# MP-Ethernet.net
KiCad netlist of a schematic drawn in Altium Designer
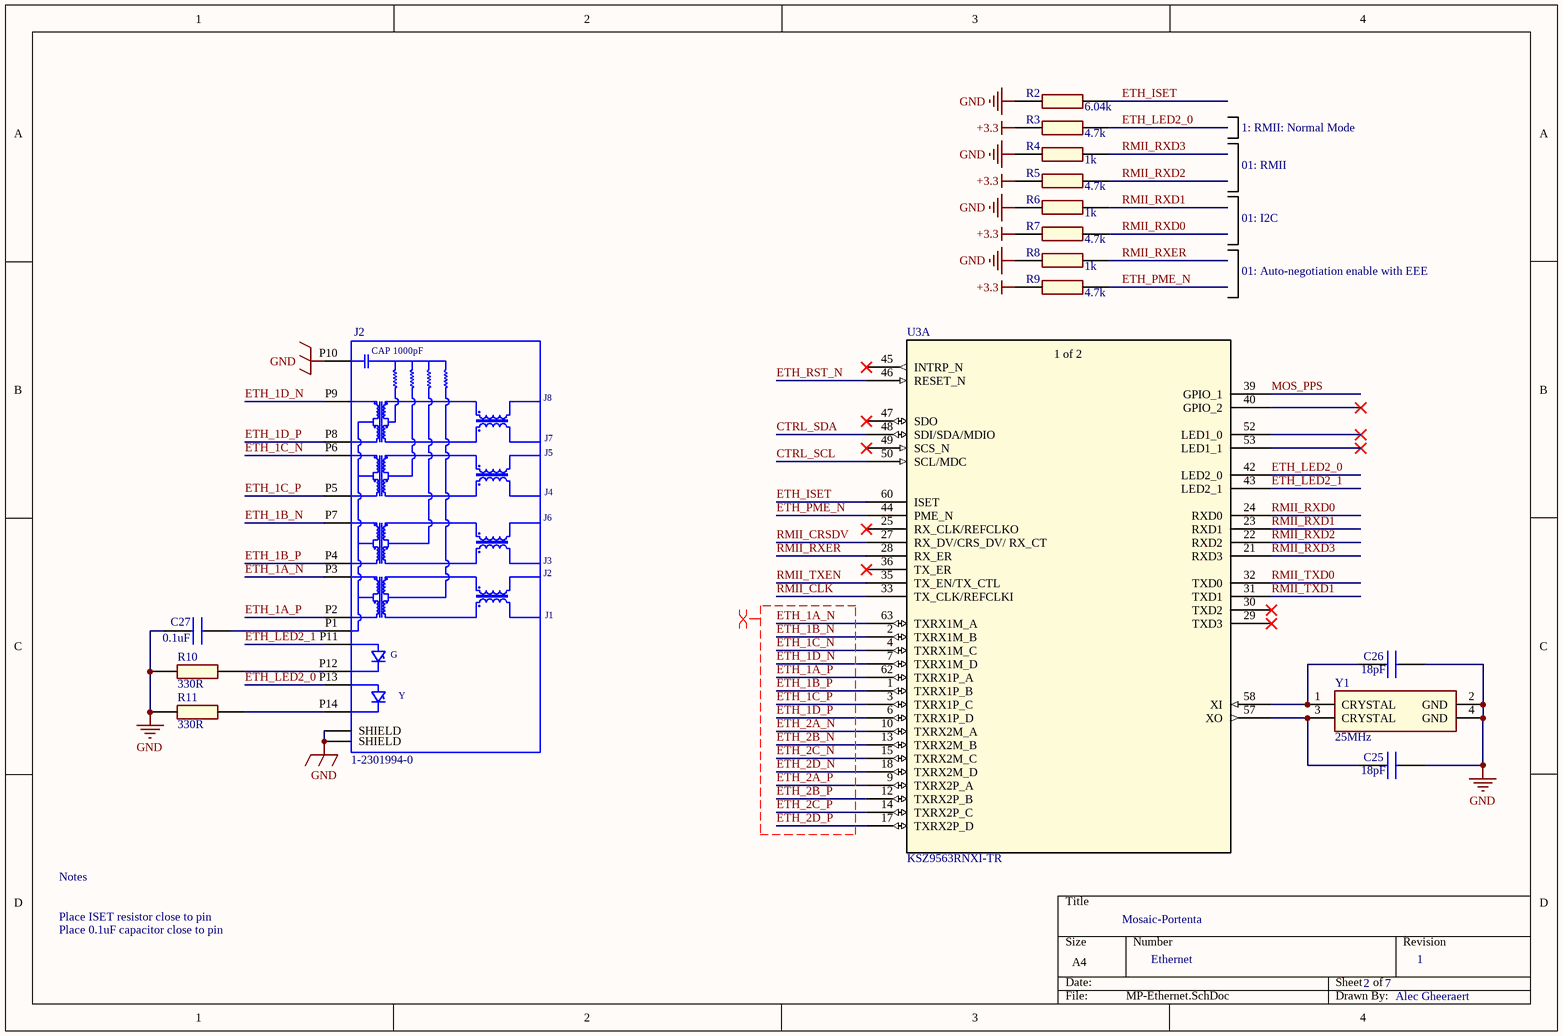
[diagram p0: MP-Ethernet.SchDoc]

(export (version "E")
  (design (tool "Eeschema 10.0.6"))
  (components
    (comp (ref "C25")
      (value "18pF")
      (footprint "CAPC1608X87N")
      (description "0603 18pF")
      (fields (field (name "TOLERANCE") "5%") (field (name "MANUFACTURER") "Walsin"))
      (libsource (lib "Ghrt") (part "0603N180J160CT"))
    )
    (comp (ref "C26")
      (value "18pF")
      (footprint "CAPC1608X87N")
      (description "0603 18pF")
      (fields (field (name "TOLERANCE") "5%") (field (name "MANUFACTURER") "Walsin"))
      (libsource (lib "Ghrt") (part "0603N180J160CT"))
    )
    (comp (ref "C27")
      (value "0.1uF")
      (footprint "CAPC2012X145N")
      (description "0805I 0.1µF")
      (fields (field (name "MANUFACTURER") "Walsin") (field (name "TOLERANCE") "10%"))
      (libsource (lib "Ghrt") (part "MG21B104K101CT"))
    )
    (comp (ref "J2")
      (value "1-2301994-0")
      (footprint "1-2301994-0")
      (description "RJ45 1Gbit MJ")
      (fields (field (name "MANUFACTURER") "TE Connectivity"))
      (libsource (lib "Ghrt") (part "1-2301994-0"))
    )
    (comp (ref "R2")
      (value "6.04k")
      (footprint "RESC1005X40N")
      (description "0402I 6.04k")
      (fields (field (name "MANUFACTURER") "Walsin") (field (name "TOLERANCE") "1%"))
      (libsource (lib "Ghrt") (part "WR04X6041FTL"))
    )
    (comp (ref "R3")
      (value "4.7k")
      (footprint "RESC1005X40N")
      (description "0402I 4.7k")
      (fields (field (name "MANUFACTURER") "Walsin") (field (name "TOLERANCE") "1%"))
      (libsource (lib "Ghrt") (part "WR04X4701FTL"))
    )
    (comp (ref "R4")
      (value "1k")
      (footprint "RESC1005X40N")
      (description "0402I 1k")
      (fields (field (name "MANUFACTURER") "Walsin") (field (name "TOLERANCE") "1%"))
      (libsource (lib "Ghrt") (part "WR04X1001FTL"))
    )
    (comp (ref "R5")
      (value "4.7k")
      (footprint "RESC1005X40N")
      (description "0402I 4.7k")
      (fields (field (name "MANUFACTURER") "Walsin") (field (name "TOLERANCE") "1%"))
      (libsource (lib "Ghrt") (part "WR04X4701FTL"))
    )
    (comp (ref "R6")
      (value "1k")
      (footprint "RESC1005X40N")
      (description "0402I 1k")
      (fields (field (name "MANUFACTURER") "Walsin") (field (name "TOLERANCE") "1%"))
      (libsource (lib "Ghrt") (part "WR04X1001FTL"))
    )
    (comp (ref "R7")
      (value "4.7k")
      (footprint "RESC1005X40N")
      (description "0402I 4.7k")
      (fields (field (name "MANUFACTURER") "Walsin") (field (name "TOLERANCE") "1%"))
      (libsource (lib "Ghrt") (part "WR04X4701FTL"))
    )
    (comp (ref "R8")
      (value "1k")
      (footprint "RESC1005X40N")
      (description "0402I 1k")
      (fields (field (name "MANUFACTURER") "Walsin") (field (name "TOLERANCE") "1%"))
      (libsource (lib "Ghrt") (part "WR04X1001FTL"))
    )
    (comp (ref "R9")
      (value "4.7k")
      (footprint "RESC1005X40N")
      (description "0402I 4.7k")
      (fields (field (name "MANUFACTURER") "Walsin") (field (name "TOLERANCE") "1%"))
      (libsource (lib "Ghrt") (part "WR04X4701FTL"))
    )
    (comp (ref "R10")
      (value "330R")
      (footprint "RESC1005X40N")
      (description "0402I 330")
      (fields (field (name "TOLERANCE") "1%") (field (name "MANUFACTURER") "Walsin"))
      (libsource (lib "Ghrt") (part "WR04X3300FTL"))
    )
    (comp (ref "R11")
      (value "330R")
      (footprint "RESC1005X40N")
      (description "0402I 330")
      (fields (field (name "TOLERANCE") "1%") (field (name "MANUFACTURER") "Walsin"))
      (libsource (lib "Ghrt") (part "WR04X3300FTL"))
    )
    (comp (ref "U3")
      (value "KSZ9563RNXI-TR")
      (footprint "VQFN64_NX_MCH")
      (description "3-Port Gigabit Ethernet Switch")
      (fields (field (name "MANUFACTURER") "Texas Instruments"))
      (libsource (lib "Ghrt") (part "KSZ9563RNXI-TR"))
    )
    (comp (ref "Y1")
      (value "25MHz")
      (footprint "LFXTAL055474REEL")
      (description "25MHz +/-50ppm Crystal")
      (fields (field (name "MANUFACTURER") "IQD") (field (name "TOLERANCE") "50PPM"))
      (libsource (lib "Ghrt") (part "LFXTAL055474REEL"))
    )
  )
  (nets
    (net (code "1") (name "+3.3") (class "Default")
      (node (ref "R3") (pin "1") (pinfunction "1_1") (pintype "passive"))
      (node (ref "R5") (pin "1") (pinfunction "1_1") (pintype "passive"))
      (node (ref "R7") (pin "1") (pinfunction "1_1") (pintype "passive"))
      (node (ref "R9") (pin "1") (pinfunction "1_1") (pintype "passive"))
    )
    (net (code "2") (name "/CTRL_SCL") (class "Default")
      (node (ref "U3") (pin "50") (pinfunction "SCL/MDC_50") (pintype "input"))
    )
    (net (code "3") (name "/CTRL_SDA") (class "Default")
      (node (ref "U3") (pin "48") (pinfunction "SDI/SDA/MDIO_48") (pintype "bidirectional"))
    )
    (net (code "4") (name "/ETH_1A_N") (class "Default")
      (node (ref "J2") (pin "P3") (pinfunction "P3_P3") (pintype "passive"))
      (node (ref "U3") (pin "63") (pinfunction "TXRX1M_A_63") (pintype "bidirectional"))
    )
    (net (code "5") (name "/ETH_1A_P") (class "Default")
      (node (ref "J2") (pin "P2") (pinfunction "P2_P2") (pintype "passive"))
      (node (ref "U3") (pin "62") (pinfunction "TXRX1P_A_62") (pintype "bidirectional"))
    )
    (net (code "6") (name "/ETH_1B_N") (class "Default")
      (node (ref "J2") (pin "P7") (pinfunction "P7_P7") (pintype "passive"))
      (node (ref "U3") (pin "2") (pinfunction "TXRX1M_B_2") (pintype "bidirectional"))
    )
    (net (code "7") (name "/ETH_1B_P") (class "Default")
      (node (ref "J2") (pin "P4") (pinfunction "P4_P4") (pintype "passive"))
      (node (ref "U3") (pin "1") (pinfunction "TXRX1P_B_1") (pintype "bidirectional"))
    )
    (net (code "8") (name "/ETH_1C_N") (class "Default")
      (node (ref "J2") (pin "P6") (pinfunction "P6_P6") (pintype "passive"))
      (node (ref "U3") (pin "4") (pinfunction "TXRX1M_C_4") (pintype "bidirectional"))
    )
    (net (code "9") (name "/ETH_1C_P") (class "Default")
      (node (ref "J2") (pin "P5") (pinfunction "P5_P5") (pintype "passive"))
      (node (ref "U3") (pin "3") (pinfunction "TXRX1P_C_3") (pintype "bidirectional"))
    )
    (net (code "10") (name "/ETH_1D_N") (class "Default")
      (node (ref "J2") (pin "P9") (pinfunction "P9_P9") (pintype "passive"))
      (node (ref "U3") (pin "7") (pinfunction "TXRX1M_D_7") (pintype "bidirectional"))
    )
    (net (code "11") (name "/ETH_1D_P") (class "Default")
      (node (ref "J2") (pin "P8") (pinfunction "P8_P8") (pintype "passive"))
      (node (ref "U3") (pin "6") (pinfunction "TXRX1P_D_6") (pintype "bidirectional"))
    )
    (net (code "12") (name "/ETH_2A_N") (class "Default")
      (node (ref "U3") (pin "10") (pinfunction "TXRX2M_A_10") (pintype "bidirectional"))
    )
    (net (code "13") (name "/ETH_2A_P") (class "Default")
      (node (ref "U3") (pin "9") (pinfunction "TXRX2P_A_9") (pintype "bidirectional"))
    )
    (net (code "14") (name "/ETH_2B_N") (class "Default")
      (node (ref "U3") (pin "13") (pinfunction "TXRX2M_B_13") (pintype "bidirectional"))
    )
    (net (code "15") (name "/ETH_2B_P") (class "Default")
      (node (ref "U3") (pin "12") (pinfunction "TXRX2P_B_12") (pintype "bidirectional"))
    )
    (net (code "16") (name "/ETH_2C_N") (class "Default")
      (node (ref "U3") (pin "15") (pinfunction "TXRX2M_C_15") (pintype "bidirectional"))
    )
    (net (code "17") (name "/ETH_2C_P") (class "Default")
      (node (ref "U3") (pin "14") (pinfunction "TXRX2P_C_14") (pintype "bidirectional"))
    )
    (net (code "18") (name "/ETH_2D_N") (class "Default")
      (node (ref "U3") (pin "18") (pinfunction "TXRX2M_D_18") (pintype "bidirectional"))
    )
    (net (code "19") (name "/ETH_2D_P") (class "Default")
      (node (ref "U3") (pin "17") (pinfunction "TXRX2P_D_17") (pintype "bidirectional"))
    )
    (net (code "20") (name "/ETH_ISET") (class "Default")
      (node (ref "R2") (pin "2") (pinfunction "2_2") (pintype "passive"))
      (node (ref "U3") (pin "60") (pinfunction "ISET_60") (pintype "passive"))
    )
    (net (code "21") (name "/ETH_LED2_0") (class "Default")
      (node (ref "J2") (pin "P13") (pinfunction "P13_P13") (pintype "passive"))
      (node (ref "R3") (pin "2") (pinfunction "2_2") (pintype "passive"))
      (node (ref "U3") (pin "42") (pinfunction "LED2_0_42") (pintype "passive"))
    )
    (net (code "22") (name "/ETH_LED2_1") (class "Default")
      (node (ref "J2") (pin "P11") (pinfunction "P11_P11") (pintype "passive"))
      (node (ref "U3") (pin "43") (pinfunction "LED2_1_43") (pintype "passive"))
    )
    (net (code "23") (name "/ETH_PME_N") (class "Default")
      (node (ref "R9") (pin "2") (pinfunction "2_2") (pintype "passive"))
      (node (ref "U3") (pin "44") (pinfunction "PME_N_44") (pintype "passive"))
    )
    (net (code "24") (name "/ETH_RST_N") (class "Default")
      (node (ref "U3") (pin "46") (pinfunction "RESET_N_46") (pintype "input"))
    )
    (net (code "25") (name "/MOS_PPS") (class "Default")
      (node (ref "U3") (pin "39") (pinfunction "GPIO_1_39") (pintype "passive"))
    )
    (net (code "26") (name "/RMII_CLK") (class "Default")
      (node (ref "U3") (pin "33") (pinfunction "TX_CLK/REFCLKI_33") (pintype "passive"))
    )
    (net (code "27") (name "/RMII_CRSDV") (class "Default")
      (node (ref "U3") (pin "27") (pinfunction "RX_DV/CRS_DV/_RX_CT_27") (pintype "passive"))
    )
    (net (code "28") (name "/RMII_RXD0") (class "Default")
      (node (ref "R7") (pin "2") (pinfunction "2_2") (pintype "passive"))
      (node (ref "U3") (pin "24") (pinfunction "RXD0_24") (pintype "passive"))
    )
    (net (code "29") (name "/RMII_RXD1") (class "Default")
      (node (ref "R6") (pin "2") (pinfunction "2_2") (pintype "passive"))
      (node (ref "U3") (pin "23") (pinfunction "RXD1_23") (pintype "passive"))
    )
    (net (code "30") (name "/RMII_RXD2") (class "Default")
      (node (ref "R5") (pin "2") (pinfunction "2_2") (pintype "passive"))
      (node (ref "U3") (pin "22") (pinfunction "RXD2_22") (pintype "passive"))
    )
    (net (code "31") (name "/RMII_RXD3") (class "Default")
      (node (ref "R4") (pin "2") (pinfunction "2_2") (pintype "passive"))
      (node (ref "U3") (pin "21") (pinfunction "RXD3_21") (pintype "passive"))
    )
    (net (code "32") (name "/RMII_RXER") (class "Default")
      (node (ref "R8") (pin "2") (pinfunction "2_2") (pintype "passive"))
      (node (ref "U3") (pin "28") (pinfunction "RX_ER_28") (pintype "passive"))
    )
    (net (code "33") (name "/RMII_TXD0") (class "Default")
      (node (ref "U3") (pin "32") (pinfunction "TXD0_32") (pintype "passive"))
    )
    (net (code "34") (name "/RMII_TXD1") (class "Default")
      (node (ref "U3") (pin "31") (pinfunction "TXD1_31") (pintype "passive"))
    )
    (net (code "35") (name "/RMII_TXEN") (class "Default")
      (node (ref "U3") (pin "35") (pinfunction "TX_EN/TX_CTL_35") (pintype "passive"))
    )
    (net (code "36") (name "GND") (class "Default")
      (node (ref "C25") (pin "2") (pinfunction "2_2") (pintype "passive"))
      (node (ref "C26") (pin "2") (pinfunction "2_2") (pintype "passive"))
      (node (ref "C27") (pin "2") (pinfunction "2_2") (pintype "passive"))
      (node (ref "J2") (pin "P10") (pinfunction "P10_P10") (pintype "passive"))
      (node (ref "J2") (pin "S1") (pinfunction "SHIELD_S1") (pintype "power_in"))
      (node (ref "J2") (pin "S2") (pinfunction "SHIELD_S2") (pintype "power_in"))
      (node (ref "R10") (pin "2") (pinfunction "2_2") (pintype "passive"))
      (node (ref "R11") (pin "2") (pinfunction "2_2") (pintype "passive"))
      (node (ref "R2") (pin "1") (pinfunction "1_1") (pintype "passive"))
      (node (ref "R4") (pin "1") (pinfunction "1_1") (pintype "passive"))
      (node (ref "R6") (pin "1") (pinfunction "1_1") (pintype "passive"))
      (node (ref "R8") (pin "1") (pinfunction "1_1") (pintype "passive"))
      (node (ref "Y1") (pin "2") (pinfunction "GND_2") (pintype "passive"))
      (node (ref "Y1") (pin "4") (pinfunction "GND_4") (pintype "passive"))
    )
    (net (code "37") (name "Net-(C27-Pad1)") (class "Default")
      (node (ref "C27") (pin "1") (pinfunction "1_1") (pintype "passive"))
      (node (ref "J2") (pin "P1") (pinfunction "P1_P1") (pintype "passive"))
    )
    (net (code "38") (name "Net-(J2-PadP12)") (class "Default")
      (node (ref "J2") (pin "P12") (pinfunction "P12_P12") (pintype "passive"))
      (node (ref "R10") (pin "1") (pinfunction "1_1") (pintype "passive"))
    )
    (net (code "39") (name "Net-(J2-PadP14)") (class "Default")
      (node (ref "J2") (pin "P14") (pinfunction "P14_P14") (pintype "passive"))
      (node (ref "R11") (pin "1") (pinfunction "1_1") (pintype "passive"))
    )
    (net (code "40") (name "Net-(U3A-XI)") (class "Default")
      (node (ref "C26") (pin "1") (pinfunction "1_1") (pintype "passive"))
      (node (ref "U3") (pin "58") (pinfunction "XI_58") (pintype "input"))
      (node (ref "Y1") (pin "1") (pinfunction "CRYSTAL_1") (pintype "passive"))
    )
    (net (code "41") (name "Net-(U3A-XO)") (class "Default")
      (node (ref "C25") (pin "1") (pinfunction "1_1") (pintype "passive"))
      (node (ref "U3") (pin "57") (pinfunction "XO_57") (pintype "output"))
      (node (ref "Y1") (pin "3") (pinfunction "CRYSTAL_3") (pintype "passive"))
    )
    (net (code "42") (name "unconnected-(U3A-GPIO_2-Pad40)") (class "Default")
      (node (ref "U3") (pin "40") (pinfunction "GPIO_2_40") (pintype "passive+no_connect"))
    )
    (net (code "43") (name "unconnected-(U3A-INTRP_N-Pad45)") (class "Default")
      (node (ref "U3") (pin "45") (pinfunction "INTRP_N_45") (pintype "output+no_connect"))
    )
    (net (code "44") (name "unconnected-(U3A-LED1_0-Pad52)") (class "Default")
      (node (ref "U3") (pin "52") (pinfunction "LED1_0_52") (pintype "passive+no_connect"))
    )
    (net (code "45") (name "unconnected-(U3A-LED1_1-Pad53)") (class "Default")
      (node (ref "U3") (pin "53") (pinfunction "LED1_1_53") (pintype "passive+no_connect"))
    )
    (net (code "46") (name "unconnected-(U3A-RX_CLK{slash}REFCLKO-Pad25)") (class "Default")
      (node (ref "U3") (pin "25") (pinfunction "RX_CLK/REFCLKO_25") (pintype "passive+no_connect"))
    )
    (net (code "47") (name "unconnected-(U3A-SCS_N-Pad49)") (class "Default")
      (node (ref "U3") (pin "49") (pinfunction "SCS_N_49") (pintype "input+no_connect"))
    )
    (net (code "48") (name "unconnected-(U3A-SDO-Pad47)") (class "Default")
      (node (ref "U3") (pin "47") (pinfunction "SDO_47") (pintype "bidirectional+no_connect"))
    )
    (net (code "49") (name "unconnected-(U3A-TXD2-Pad30)") (class "Default")
      (node (ref "U3") (pin "30") (pinfunction "TXD2_30") (pintype "passive+no_connect"))
    )
    (net (code "50") (name "unconnected-(U3A-TXD3-Pad29)") (class "Default")
      (node (ref "U3") (pin "29") (pinfunction "TXD3_29") (pintype "passive+no_connect"))
    )
    (net (code "51") (name "unconnected-(U3A-TX_ER-Pad36)") (class "Default")
      (node (ref "U3") (pin "36") (pinfunction "TX_ER_36") (pintype "passive+no_connect"))
    )
  )
)
